# untitled.net
KiCad netlist of a schematic drawn in EAGLE
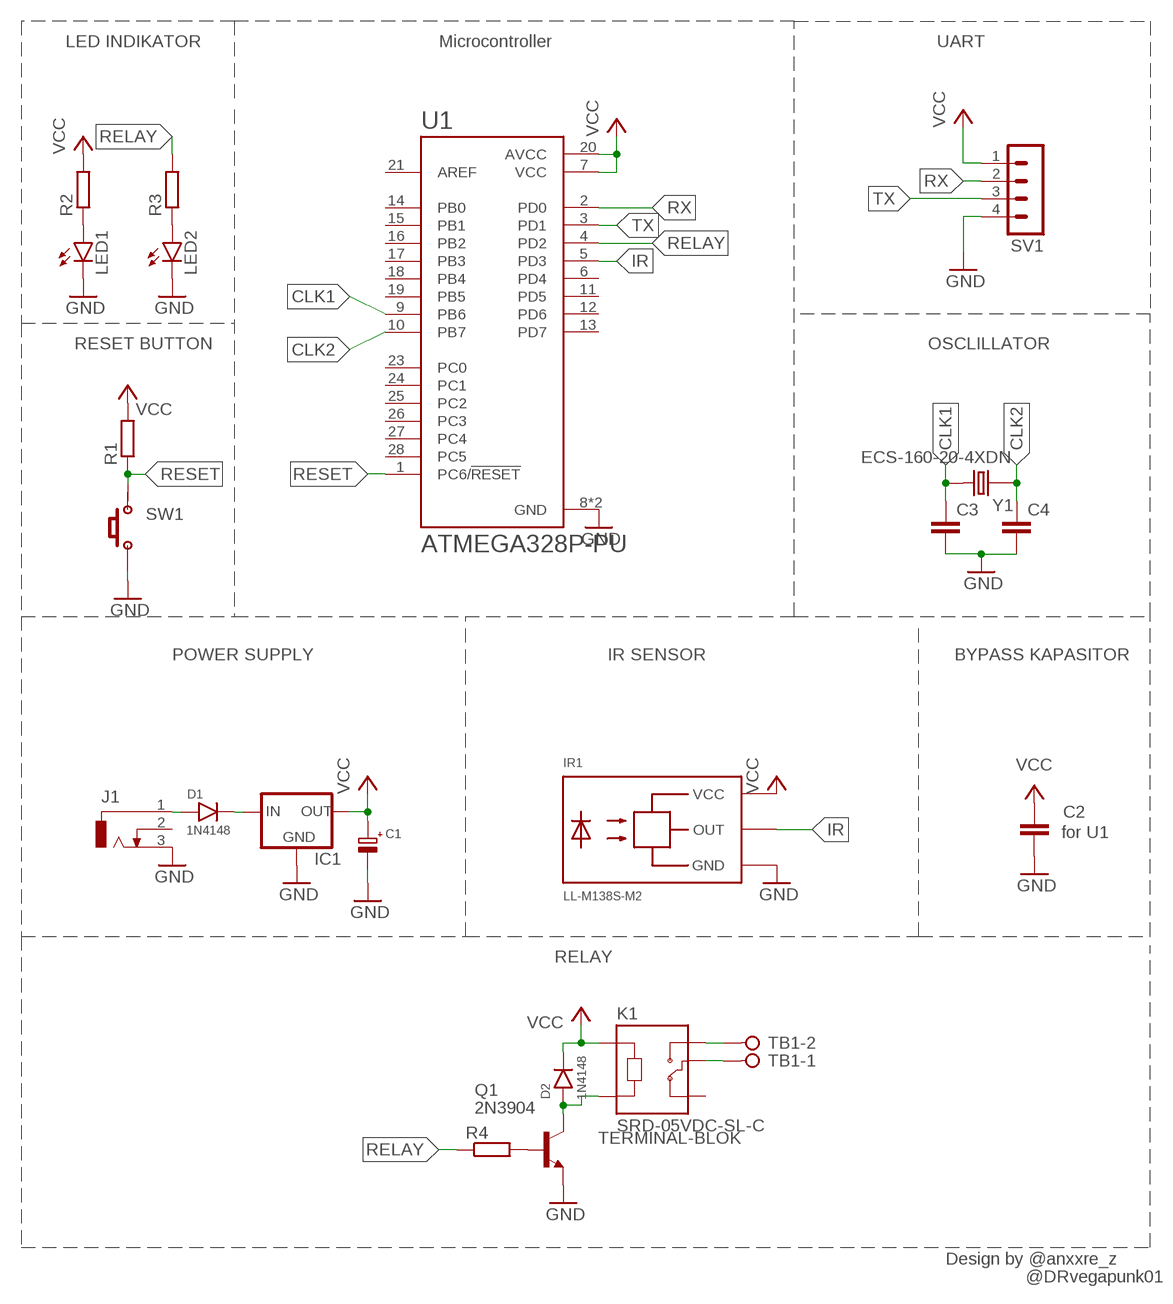
[diagram p0: schematic, sheet 1]

(export (version "E")
  (design (tool "Eeschema 10.0.6"))
  (components
    (comp (ref "C1")
      (value "CAP-ELCO")
      (footprint "eagle-import:ELCO1")
      (libsource (lib "eagle-import") (part "CAP-ELCO"))
    )
    (comp (ref "C2")
      (value "CAP-NON")
      (footprint "eagle-import:MKM")
      (libsource (lib "eagle-import") (part "CAP-NON"))
    )
    (comp (ref "C3")
      (value "C-EU025-025X050")
      (footprint "eagle-import:C025-025X050")
      (libsource (lib "eagle-import") (part "C-EU025-025X050"))
    )
    (comp (ref "C4")
      (value "C-EU025-025X050")
      (footprint "eagle-import:C025-025X050")
      (libsource (lib "eagle-import") (part "C-EU025-025X050"))
    )
    (comp (ref "D1")
      (value "1N4148")
      (footprint "eagle-import:DIODE")
      (libsource (lib "eagle-import") (part "1N4148"))
    )
    (comp (ref "D2")
      (value "1N4148")
      (footprint "eagle-import:DIODE")
      (libsource (lib "eagle-import") (part "1N4148"))
    )
    (comp (ref "IC1")
      (value "78XXS")
      (footprint "eagle-import:78XXS")
      (libsource (lib "eagle-import") (part "78XXS"))
    )
    (comp (ref "IR1")
      (value "LL-M138S-M2")
      (footprint "eagle-import:LL-M138S-M2")
      (libsource (lib "eagle-import") (part "LL-M138S-M2"))
    )
    (comp (ref "J1")
      (value "DCJ0303")
      (footprint "eagle-import:DCJ0303")
      (libsource (lib "eagle-import") (part "DCJ0303"))
    )
    (comp (ref "K1")
      (value "SRD-05VDC-SL-C")
      (footprint "eagle-import:RELAY_SRD-05VDC-SL-C")
      (fields (field (name "MANUFACTURER") "SONGLE RELAY"))
      (libsource (lib "eagle-import") (part "SRD-05VDC-SL-C"))
    )
    (comp (ref "LED1")
      (value "LED5MM")
      (footprint "eagle-import:LED5MM")
      (libsource (lib "eagle-import") (part "LED5MM"))
    )
    (comp (ref "LED2")
      (value "LED5MM")
      (footprint "eagle-import:LED5MM")
      (libsource (lib "eagle-import") (part "LED5MM"))
    )
    (comp (ref "Q1")
      (value "2N3904")
      (footprint "eagle-import:TO92-EBC")
      (libsource (lib "eagle-import") (part "2N3904"))
    )
    (comp (ref "R1")
      (value "RES0207/10")
      (footprint "eagle-import:0207_10")
      (libsource (lib "eagle-import") (part "RES0207/10"))
    )
    (comp (ref "R2")
      (value "RES0207/10")
      (footprint "eagle-import:0207_10")
      (libsource (lib "eagle-import") (part "RES0207/10"))
    )
    (comp (ref "R3")
      (value "RES0207/10")
      (footprint "eagle-import:0207_10")
      (libsource (lib "eagle-import") (part "RES0207/10"))
    )
    (comp (ref "R4")
      (value "RES0207/10")
      (footprint "eagle-import:0207_10")
      (libsource (lib "eagle-import") (part "RES0207/10"))
    )
    (comp (ref "SV1")
      (value "MA04-1")
      (footprint "eagle-import:MA04-1")
      (libsource (lib "eagle-import") (part "MA04-1"))
    )
    (comp (ref "SW1")
      (value "PUSH_BUTTON4P")
      (footprint "eagle-import:PUSH_BUTTON_4P")
      (libsource (lib "eagle-import") (part "PUSH_BUTTON4P"))
    )
    (comp (ref "TB1")
      (value "TERMINAL-BLOK")
      (footprint "eagle-import:TB-2P")
      (libsource (lib "eagle-import") (part "TERMINAL-BLOK"))
    )
    (comp (ref "U1")
      (value "ATMEGA328P-PU")
      (footprint "eagle-import:DIP794W46P254L2967H457Q28B")
      (fields (field (name "MANUFACTURER") "Atmel"))
      (libsource (lib "eagle-import") (part "ATMEGA328P-PU"))
    )
    (comp (ref "Y1")
      (value "ECS-160-20-4XDN")
      (footprint "eagle-import:XTAL_ECS-160-20-4XDN")
      (fields (field (name "MANUFACTURER") "ECS Inc."))
      (libsource (lib "eagle-import") (part "ECS-160-20-4XDN"))
    )
  )
  (nets
    (net (code "1") (name "CLK1") (class "Default")
      (node (ref "C3") (pin "1") (pinfunction "1_1") (pintype "passive"))
      (node (ref "U1") (pin "9") (pinfunction "PB6_9") (pintype "bidirectional"))
      (node (ref "Y1") (pin "2") (pinfunction "2_2") (pintype "passive"))
    )
    (net (code "2") (name "CLK2") (class "Default")
      (node (ref "C4") (pin "1") (pinfunction "1_1") (pintype "passive"))
      (node (ref "U1") (pin "10") (pinfunction "PB7_10") (pintype "bidirectional"))
      (node (ref "Y1") (pin "1") (pinfunction "1_1") (pintype "passive"))
    )
    (net (code "3") (name "GND") (class "Default")
      (node (ref "C1") (pin "2") (pinfunction "2_2") (pintype "bidirectional"))
      (node (ref "C2") (pin "2") (pinfunction "2_2") (pintype "passive"))
      (node (ref "C3") (pin "2") (pinfunction "2_2") (pintype "passive"))
      (node (ref "C4") (pin "2") (pinfunction "2_2") (pintype "passive"))
      (node (ref "IC1") (pin "GND") (pinfunction "GND_GND") (pintype "input"))
      (node (ref "IR1") (pin "GND") (pinfunction "GND_GND") (pintype "power_in"))
      (node (ref "J1") (pin "3") (pinfunction "3_3") (pintype "passive"))
      (node (ref "LED1") (pin "K") (pinfunction "C_K") (pintype "passive"))
      (node (ref "LED2") (pin "K") (pinfunction "C_K") (pintype "passive"))
      (node (ref "Q1") (pin "E") (pinfunction "E_E") (pintype "passive"))
      (node (ref "SV1") (pin "4") (pinfunction "4_4") (pintype "passive"))
      (node (ref "SW1") (pin "1") (pinfunction "1_1") (pintype "bidirectional"))
      (node (ref "SW1") (pin "2") (pinfunction "1_2") (pintype "bidirectional"))
      (node (ref "U1") (pin "22") (pinfunction "GND_22") (pintype "power_in"))
      (node (ref "U1") (pin "8") (pinfunction "GND_8") (pintype "power_in"))
    )
    (net (code "4") (name "IR") (class "Default")
      (node (ref "IR1") (pin "OUT") (pinfunction "OUT_OUT") (pintype "output"))
      (node (ref "U1") (pin "5") (pinfunction "PD3_5") (pintype "bidirectional"))
    )
    (net (code "5") (name "Net-(D1-Pad1)") (class "Default")
      (node (ref "D1") (pin "1") (pinfunction "1_1") (pintype "bidirectional"))
      (node (ref "J1") (pin "1") (pinfunction "1_1") (pintype "passive"))
    )
    (net (code "6") (name "Net-(D1-Pad2)") (class "Default")
      (node (ref "D1") (pin "2") (pinfunction "2_2") (pintype "bidirectional"))
      (node (ref "IC1") (pin "IN") (pinfunction "IN_IN") (pintype "input"))
    )
    (net (code "7") (name "Net-(D2-Pad1)") (class "Default")
      (node (ref "D2") (pin "1") (pinfunction "1_1") (pintype "bidirectional"))
      (node (ref "K1") (pin "A2") (pinfunction "A2_A2") (pintype "passive"))
      (node (ref "Q1") (pin "C") (pinfunction "C_C") (pintype "passive"))
    )
    (net (code "8") (name "Net-(LED1-PadA)") (class "Default")
      (node (ref "LED1") (pin "A") (pinfunction "A_A") (pintype "passive"))
      (node (ref "R2") (pin "1") (pinfunction "1_1") (pintype "passive"))
    )
    (net (code "9") (name "Net-(LED2-PadA)") (class "Default")
      (node (ref "LED2") (pin "A") (pinfunction "A_A") (pintype "passive"))
      (node (ref "R3") (pin "1") (pinfunction "1_1") (pintype "passive"))
    )
    (net (code "10") (name "Net-(Q1-PadB)") (class "Default")
      (node (ref "Q1") (pin "B") (pinfunction "B_B") (pintype "passive"))
      (node (ref "R4") (pin "2") (pinfunction "2_2") (pintype "passive"))
    )
    (net (code "11") (name "Net-(TB1A-KL)") (class "Default")
      (node (ref "K1") (pin "COM") (pinfunction "COM_COM") (pintype "passive"))
      (node (ref "TB1") (pin "1") (pinfunction "KL_1") (pintype "passive"))
    )
    (net (code "12") (name "Net-(TB1B-KL)") (class "Default")
      (node (ref "K1") (pin "NO") (pinfunction "NO_NO") (pintype "passive"))
      (node (ref "TB1") (pin "2") (pinfunction "KL_2") (pintype "passive"))
    )
    (net (code "13") (name "RELAY") (class "Default")
      (node (ref "R3") (pin "2") (pinfunction "2_2") (pintype "passive"))
      (node (ref "R4") (pin "1") (pinfunction "1_1") (pintype "passive"))
      (node (ref "U1") (pin "4") (pinfunction "PD2_4") (pintype "bidirectional"))
    )
    (net (code "14") (name "RESET") (class "Default")
      (node (ref "R1") (pin "1") (pinfunction "1_1") (pintype "passive"))
      (node (ref "SW1") (pin "3") (pinfunction "2_3") (pintype "bidirectional"))
      (node (ref "SW1") (pin "4") (pinfunction "2_4") (pintype "bidirectional"))
      (node (ref "U1") (pin "1") (pinfunction "PC6/~{RESET}_1") (pintype "bidirectional"))
    )
    (net (code "15") (name "RX") (class "Default")
      (node (ref "SV1") (pin "2") (pinfunction "2_2") (pintype "passive"))
      (node (ref "U1") (pin "2") (pinfunction "PD0_2") (pintype "bidirectional"))
    )
    (net (code "16") (name "TX") (class "Default")
      (node (ref "SV1") (pin "3") (pinfunction "3_3") (pintype "passive"))
      (node (ref "U1") (pin "3") (pinfunction "PD1_3") (pintype "bidirectional"))
    )
    (net (code "17") (name "VCC") (class "Default")
      (node (ref "C1") (pin "1") (pinfunction "1_1") (pintype "bidirectional"))
      (node (ref "C2") (pin "1") (pinfunction "1_1") (pintype "passive"))
      (node (ref "D2") (pin "2") (pinfunction "2_2") (pintype "bidirectional"))
      (node (ref "IC1") (pin "OUT") (pinfunction "OUT_OUT") (pintype "passive"))
      (node (ref "IR1") (pin "VCC") (pinfunction "VCC_VCC") (pintype "power_in"))
      (node (ref "K1") (pin "A1") (pinfunction "A1_A1") (pintype "passive"))
      (node (ref "R1") (pin "2") (pinfunction "2_2") (pintype "passive"))
      (node (ref "R2") (pin "2") (pinfunction "2_2") (pintype "passive"))
      (node (ref "SV1") (pin "1") (pinfunction "1_1") (pintype "passive"))
      (node (ref "U1") (pin "20") (pinfunction "AVCC_20") (pintype "power_in"))
      (node (ref "U1") (pin "7") (pinfunction "VCC_7") (pintype "power_in"))
    )
    (net (code "18") (name "unconnected-(J1-Pad2)") (class "Default")
      (node (ref "J1") (pin "2") (pinfunction "2_2") (pintype "passive"))
    )
    (net (code "19") (name "unconnected-(K1-PadNC)") (class "Default")
      (node (ref "K1") (pin "NC") (pinfunction "NC_NC") (pintype "passive"))
    )
    (net (code "20") (name "unconnected-(U1-AREF-Pad21)") (class "Default")
      (node (ref "U1") (pin "21") (pinfunction "AREF_21") (pintype "input"))
    )
    (net (code "21") (name "unconnected-(U1-PB0-Pad14)") (class "Default")
      (node (ref "U1") (pin "14") (pinfunction "PB0_14") (pintype "bidirectional"))
    )
    (net (code "22") (name "unconnected-(U1-PB1-Pad15)") (class "Default")
      (node (ref "U1") (pin "15") (pinfunction "PB1_15") (pintype "bidirectional"))
    )
    (net (code "23") (name "unconnected-(U1-PB2-Pad16)") (class "Default")
      (node (ref "U1") (pin "16") (pinfunction "PB2_16") (pintype "bidirectional"))
    )
    (net (code "24") (name "unconnected-(U1-PB3-Pad17)") (class "Default")
      (node (ref "U1") (pin "17") (pinfunction "PB3_17") (pintype "bidirectional"))
    )
    (net (code "25") (name "unconnected-(U1-PB4-Pad18)") (class "Default")
      (node (ref "U1") (pin "18") (pinfunction "PB4_18") (pintype "bidirectional"))
    )
    (net (code "26") (name "unconnected-(U1-PB5-Pad19)") (class "Default")
      (node (ref "U1") (pin "19") (pinfunction "PB5_19") (pintype "bidirectional"))
    )
    (net (code "27") (name "unconnected-(U1-PC0-Pad23)") (class "Default")
      (node (ref "U1") (pin "23") (pinfunction "PC0_23") (pintype "bidirectional"))
    )
    (net (code "28") (name "unconnected-(U1-PC1-Pad24)") (class "Default")
      (node (ref "U1") (pin "24") (pinfunction "PC1_24") (pintype "bidirectional"))
    )
    (net (code "29") (name "unconnected-(U1-PC2-Pad25)") (class "Default")
      (node (ref "U1") (pin "25") (pinfunction "PC2_25") (pintype "bidirectional"))
    )
    (net (code "30") (name "unconnected-(U1-PC3-Pad26)") (class "Default")
      (node (ref "U1") (pin "26") (pinfunction "PC3_26") (pintype "bidirectional"))
    )
    (net (code "31") (name "unconnected-(U1-PC4-Pad27)") (class "Default")
      (node (ref "U1") (pin "27") (pinfunction "PC4_27") (pintype "bidirectional"))
    )
    (net (code "32") (name "unconnected-(U1-PC5-Pad28)") (class "Default")
      (node (ref "U1") (pin "28") (pinfunction "PC5_28") (pintype "bidirectional"))
    )
    (net (code "33") (name "unconnected-(U1-PD4-Pad6)") (class "Default")
      (node (ref "U1") (pin "6") (pinfunction "PD4_6") (pintype "bidirectional"))
    )
    (net (code "34") (name "unconnected-(U1-PD5-Pad11)") (class "Default")
      (node (ref "U1") (pin "11") (pinfunction "PD5_11") (pintype "bidirectional"))
    )
    (net (code "35") (name "unconnected-(U1-PD6-Pad12)") (class "Default")
      (node (ref "U1") (pin "12") (pinfunction "PD6_12") (pintype "bidirectional"))
    )
    (net (code "36") (name "unconnected-(U1-PD7-Pad13)") (class "Default")
      (node (ref "U1") (pin "13") (pinfunction "PD7_13") (pintype "bidirectional"))
    )
  )
)
